# PIC.net
KiCad netlist of a schematic drawn in Altium Designer
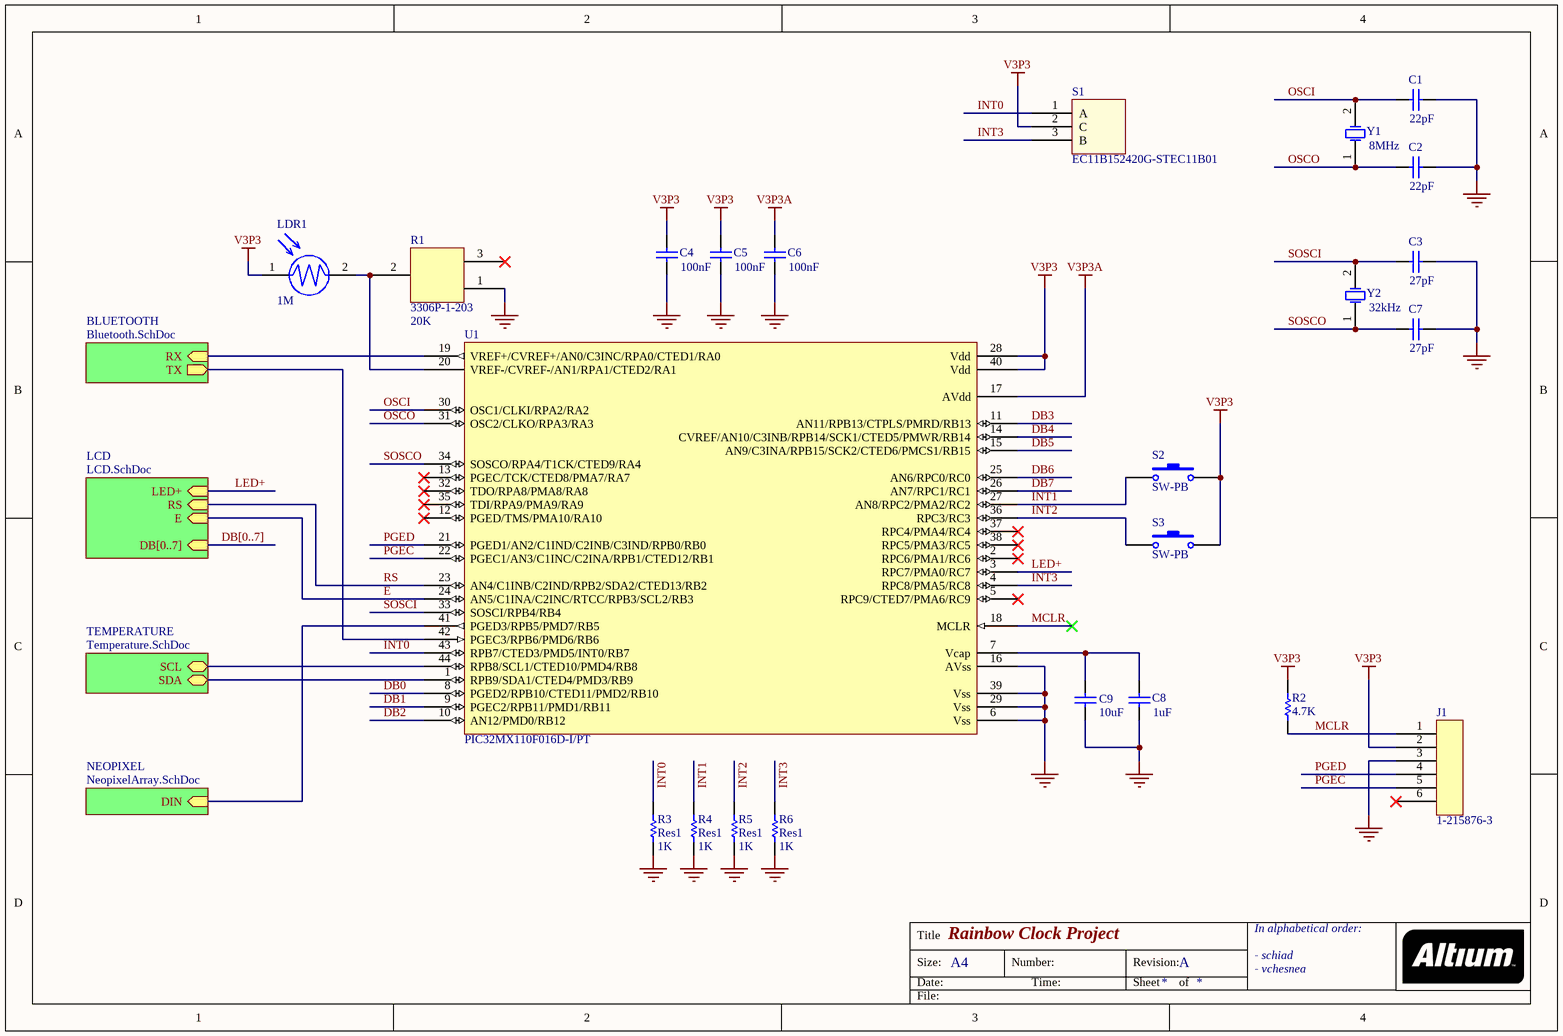
[diagram p0: PIC.SchDoc]

(export (version "E")
  (design (tool "Eeschema 10.0.6"))
  (components
    (comp (ref "C1")
      (value "22pF")
      (footprint "RAD-0.3")
      (description "Capacitor")
      (fields (field (name "Comment") "Cap"))
      (libsource (lib "Miscellaneous Devices") (part "Cap"))
    )
    (comp (ref "C2")
      (value "22pF")
      (footprint "RAD-0.3")
      (description "Capacitor")
      (fields (field (name "Comment") "Cap"))
      (libsource (lib "Miscellaneous Devices") (part "Cap"))
    )
    (comp (ref "C3")
      (value "27pF")
      (footprint "RAD-0.3")
      (description "Capacitor")
      (fields (field (name "Comment") "Cap"))
      (libsource (lib "Miscellaneous Devices") (part "Cap"))
    )
    (comp (ref "C4")
      (value "100nF")
      (footprint "RAD-0.3")
      (description "Capacitor")
      (fields (field (name "Comment") "Cap"))
      (libsource (lib "Miscellaneous Devices") (part "Cap"))
    )
    (comp (ref "C5")
      (value "100nF")
      (footprint "RAD-0.3")
      (description "Capacitor")
      (fields (field (name "Comment") "Cap"))
      (libsource (lib "Miscellaneous Devices") (part "Cap"))
    )
    (comp (ref "C6")
      (value "100nF")
      (footprint "RAD-0.3")
      (description "Capacitor")
      (fields (field (name "Comment") "Cap"))
      (libsource (lib "Miscellaneous Devices") (part "Cap"))
    )
    (comp (ref "C7")
      (value "27pF")
      (footprint "RAD-0.3")
      (description "Capacitor")
      (fields (field (name "Comment") "Cap"))
      (libsource (lib "Miscellaneous Devices") (part "Cap"))
    )
    (comp (ref "C8")
      (value "1uF")
      (footprint "RAD-0.3")
      (description "Capacitor")
      (fields (field (name "Comment") "Cap"))
      (libsource (lib "Miscellaneous Devices") (part "Cap"))
    )
    (comp (ref "C9")
      (value "10uF")
      (footprint "RAD-0.3")
      (description "Capacitor")
      (fields (field (name "Comment") "Cap"))
      (libsource (lib "Miscellaneous Devices") (part "Cap"))
    )
    (comp (ref "J1")
      (value "1-215876-3")
      (description "Tyco 1-215876-3")
      (libsource (lib "Components") (part "1-215876-3"))
    )
    (comp (ref "LDR1")
      (value "1M")
      (description "Photoresistor")
      (fields (field (name "Comment") "LDR"))
      (libsource (lib "Components") (part "LDR"))
    )
    (comp (ref "R1")
      (value "3306P-1-203")
      (footprint "3306P-1-202")
      (description "Trimpot")
      (fields (field (name "ALTIUM_VALUE") "20K"))
      (libsource (lib "Components") (part "3306P-1-202"))
    )
    (comp (ref "R2")
      (value "4.7K")
      (footprint "AXIAL-0.3")
      (description "Resistor")
      (fields (field (name "Comment") "Res1"))
      (libsource (lib "Miscellaneous Devices") (part "Res1"))
    )
    (comp (ref "R3")
      (value "Res1")
      (footprint "AXIAL-0.3")
      (description "Resistor")
      (fields (field (name "ALTIUM_VALUE") "1K"))
      (libsource (lib "Miscellaneous Devices") (part "Res1"))
    )
    (comp (ref "R4")
      (value "Res1")
      (footprint "AXIAL-0.3")
      (description "Resistor")
      (fields (field (name "ALTIUM_VALUE") "1K"))
      (libsource (lib "Miscellaneous Devices") (part "Res1"))
    )
    (comp (ref "R5")
      (value "Res1")
      (footprint "AXIAL-0.3")
      (description "Resistor")
      (fields (field (name "ALTIUM_VALUE") "1K"))
      (libsource (lib "Miscellaneous Devices") (part "Res1"))
    )
    (comp (ref "R6")
      (value "Res1")
      (footprint "AXIAL-0.3")
      (description "Resistor")
      (fields (field (name "ALTIUM_VALUE") "1K"))
      (libsource (lib "Miscellaneous Devices") (part "Res1"))
    )
    (comp (ref "S1")
      (value "EC11B152420G-STEC11B01")
      (footprint "EC11B152420G-STEC11B01")
      (description "Rotary encoder")
      (libsource (lib "Components") (part "EC11B152420G-STEC11B01"))
    )
    (comp (ref "S2")
      (value "SW-PB")
      (footprint "Button")
      (description "Switch")
      (libsource (lib "Miscellaneous Devices") (part "SW-PB"))
    )
    (comp (ref "S3")
      (value "SW-PB")
      (footprint "SPST-2")
      (description "Switch")
      (libsource (lib "Miscellaneous Devices") (part "SW-PB"))
    )
    (comp (ref "U1")
      (value "PIC32MX110F016D-I/PT")
      (description "Microcontroller")
      (libsource (lib "Components") (part "PIC32MX110F016D-I/PT"))
    )
    (comp (ref "Y1")
      (value "8MHz")
      (footprint "R38")
      (description "Crystal Oscillator")
      (fields (field (name "Comment") "XTAL"))
      (libsource (lib "Miscellaneous Devices") (part "XTAL"))
    )
    (comp (ref "Y2")
      (value "32kHz")
      (footprint "R38")
      (description "Crystal Oscillator")
      (fields (field (name "Comment") "XTAL"))
      (libsource (lib "Miscellaneous Devices") (part "XTAL"))
    )
  )
  (nets
    (net (code "1") (name "/DB0") (class "Default")
      (node (ref "U1") (pin "8") (pinfunction "PGED2/RPB10/CTED11/PMD2/RB10_8") (pintype "bidirectional"))
    )
    (net (code "2") (name "/DB1") (class "Default")
      (node (ref "U1") (pin "9") (pinfunction "PGEC2/RPB11/PMD1/RB11_9") (pintype "bidirectional"))
    )
    (net (code "3") (name "/DB2") (class "Default")
      (node (ref "U1") (pin "10") (pinfunction "AN12/PMD0/RB12_10") (pintype "bidirectional"))
    )
    (net (code "4") (name "/DB3") (class "Default")
      (node (ref "U1") (pin "11") (pinfunction "AN11/RPB13/CTPLS/PMRD/RB13_11") (pintype "bidirectional"))
    )
    (net (code "5") (name "/DB4") (class "Default")
      (node (ref "U1") (pin "14") (pinfunction "CVREF/AN10/C3INB/RPB14/SCK1/CTED5/PMWR/RB14_14") (pintype "bidirectional"))
    )
    (net (code "6") (name "/DB5") (class "Default")
      (node (ref "U1") (pin "15") (pinfunction "AN9/C3INA/RPB15/SCK2/CTED6/PMCS1/RB15_15") (pintype "bidirectional"))
    )
    (net (code "7") (name "/DB6") (class "Default")
      (node (ref "U1") (pin "25") (pinfunction "AN6/RPC0/RC0_25") (pintype "bidirectional"))
    )
    (net (code "8") (name "/DB7") (class "Default")
      (node (ref "U1") (pin "26") (pinfunction "AN7/RPC1/RC1_26") (pintype "bidirectional"))
    )
    (net (code "10") (name "/DIN") (class "Default")
      (node (ref "U1") (pin "41") (pinfunction "PGED3/RPB5/PMD7/RB5_41") (pintype "output"))
    )
    (net (code "11") (name "/E") (class "Default")
      (node (ref "U1") (pin "24") (pinfunction "AN5/C1INA/C2INC/RTCC/RPB3/SCL2/RB3_24") (pintype "bidirectional"))
    )
    (net (code "12") (name "/INT0") (class "Default")
      (node (ref "R3") (pin "1") (pinfunction "1_1") (pintype "passive"))
      (node (ref "S1") (pin "1") (pinfunction "A_1") (pintype "passive"))
      (node (ref "U1") (pin "43") (pinfunction "RPB7/CTED3/PMD5/INT0/RB7_43") (pintype "bidirectional"))
    )
    (net (code "13") (name "/INT1") (class "Default")
      (node (ref "R4") (pin "2") (pinfunction "2_2") (pintype "passive"))
      (node (ref "S2") (pin "1") (pinfunction "1_1") (pintype "passive"))
      (node (ref "U1") (pin "27") (pinfunction "AN8/RPC2/PMA2/RC2_27") (pintype "bidirectional"))
    )
    (net (code "14") (name "/INT2") (class "Default")
      (node (ref "R5") (pin "2") (pinfunction "2_2") (pintype "passive"))
      (node (ref "S3") (pin "1") (pinfunction "1_1") (pintype "passive"))
      (node (ref "U1") (pin "36") (pinfunction "RPC3/RC3_36") (pintype "bidirectional"))
    )
    (net (code "15") (name "/INT3") (class "Default")
      (node (ref "R6") (pin "2") (pinfunction "2_2") (pintype "passive"))
      (node (ref "S1") (pin "3") (pinfunction "B_3") (pintype "passive"))
      (node (ref "U1") (pin "4") (pinfunction "RPC8/PMA5/RC8_4") (pintype "bidirectional"))
    )
    (net (code "16") (name "/LED+") (class "Default")
      (node (ref "U1") (pin "3") (pinfunction "RPC7/PMA0/RC7_3") (pintype "bidirectional"))
    )
    (net (code "17") (name "/MCLR") (class "Default")
      (node (ref "J1") (pin "1") (pintype "passive"))
      (node (ref "R2") (pin "1") (pinfunction "1_1") (pintype "passive"))
      (node (ref "U1") (pin "18") (pinfunction "MCLR_18") (pintype "input"))
    )
    (net (code "18") (name "/OSCI") (class "Default")
      (node (ref "C1") (pin "1") (pinfunction "1_1") (pintype "passive"))
      (node (ref "U1") (pin "30") (pinfunction "OSC1/CLKI/RPA2/RA2_30") (pintype "bidirectional"))
      (node (ref "Y1") (pin "2") (pinfunction "OSC2_2") (pintype "passive"))
    )
    (net (code "19") (name "/OSCO") (class "Default")
      (node (ref "C2") (pin "1") (pinfunction "1_1") (pintype "passive"))
      (node (ref "U1") (pin "31") (pinfunction "OSC2/CLKO/RPA3/RA3_31") (pintype "bidirectional"))
      (node (ref "Y1") (pin "1") (pinfunction "OSC1_1") (pintype "passive"))
    )
    (net (code "20") (name "/PGEC") (class "Default")
      (node (ref "J1") (pin "5") (pintype "passive"))
      (node (ref "U1") (pin "22") (pinfunction "PGEC1/AN3/C1INC/C2INA/RPB1/CTED12/RB1_22") (pintype "bidirectional"))
    )
    (net (code "21") (name "/PGED") (class "Default")
      (node (ref "J1") (pin "4") (pintype "passive"))
      (node (ref "U1") (pin "21") (pinfunction "PGED1/AN2/C1IND/C2INB/C3IND/RPB0/RB0_21") (pintype "bidirectional"))
    )
    (net (code "22") (name "/RS") (class "Default")
      (node (ref "U1") (pin "23") (pinfunction "AN4/C1INB/C2IND/RPB2/SDA2/CTED13/RB2_23") (pintype "bidirectional"))
    )
    (net (code "23") (name "/RX") (class "Default")
      (node (ref "U1") (pin "19") (pinfunction "VREF+/CVREF+/AN0/C3INC/RPA0/CTED1/RA0_19") (pintype "output"))
    )
    (net (code "24") (name "/SCL") (class "Default")
      (node (ref "U1") (pin "44") (pinfunction "RPB8/SCL1/CTED10/PMD4/RB8_44") (pintype "bidirectional"))
    )
    (net (code "25") (name "/SDA") (class "Default")
      (node (ref "U1") (pin "1") (pinfunction "RPB9/SDA1/CTED4/PMD3/RB9_1") (pintype "bidirectional"))
    )
    (net (code "26") (name "/SOSCI") (class "Default")
      (node (ref "C3") (pin "1") (pinfunction "1_1") (pintype "passive"))
      (node (ref "U1") (pin "33") (pinfunction "SOSCI/RPB4/RB4_33") (pintype "bidirectional"))
      (node (ref "Y2") (pin "2") (pinfunction "OSC2_2") (pintype "passive"))
    )
    (net (code "27") (name "/SOSCO") (class "Default")
      (node (ref "C7") (pin "1") (pinfunction "1_1") (pintype "passive"))
      (node (ref "U1") (pin "34") (pinfunction "SOSCO/RPA4/T1CK/CTED9/RA4_34") (pintype "bidirectional"))
      (node (ref "Y2") (pin "1") (pinfunction "OSC1_1") (pintype "passive"))
    )
    (net (code "28") (name "/TX") (class "Default")
      (node (ref "U1") (pin "42") (pinfunction "PGEC3/RPB6/PMD6/RB6_42") (pintype "input"))
    )
    (net (code "29") (name "GND") (class "Default")
      (node (ref "C1") (pin "2") (pinfunction "2_2") (pintype "passive"))
      (node (ref "C2") (pin "2") (pinfunction "2_2") (pintype "passive"))
      (node (ref "C3") (pin "2") (pinfunction "2_2") (pintype "passive"))
      (node (ref "C4") (pin "1") (pinfunction "1_1") (pintype "passive"))
      (node (ref "C5") (pin "1") (pinfunction "1_1") (pintype "passive"))
      (node (ref "C6") (pin "1") (pinfunction "1_1") (pintype "passive"))
      (node (ref "C7") (pin "2") (pinfunction "2_2") (pintype "passive"))
      (node (ref "J1") (pin "3") (pintype "passive"))
      (node (ref "R1") (pin "1") (pinfunction "1_1") (pintype "power_in"))
      (node (ref "R3") (pin "2") (pinfunction "2_2") (pintype "passive"))
      (node (ref "R4") (pin "1") (pinfunction "1_1") (pintype "passive"))
      (node (ref "R5") (pin "1") (pinfunction "1_1") (pintype "passive"))
      (node (ref "R6") (pin "1") (pinfunction "1_1") (pintype "passive"))
    )
    (net (code "30") (name "Net-(U1-VREF-{slash}CVREF-{slash}AN1{slash}RPA1{slash}CTED2{slash}RA1)") (class "Default")
      (node (ref "LDR1") (pin "2") (pinfunction "2_2") (pintype "power_in"))
      (node (ref "R1") (pin "2") (pinfunction "2_2") (pintype "power_in"))
      (node (ref "U1") (pin "20") (pinfunction "VREF-/CVREF-/AN1/RPA1/CTED2/RA1_20") (pintype "passive"))
    )
    (net (code "31") (name "Net-(U1-Vcap)") (class "Default")
      (node (ref "C8") (pin "2") (pinfunction "2_2") (pintype "passive"))
      (node (ref "C9") (pin "2") (pinfunction "2_2") (pintype "passive"))
      (node (ref "U1") (pin "7") (pinfunction "Vcap_7") (pintype "power_in"))
    )
    (net (code "32") (name "V3P3") (class "Default")
      (node (ref "C4") (pin "2") (pinfunction "2_2") (pintype "passive"))
      (node (ref "C5") (pin "2") (pinfunction "2_2") (pintype "passive"))
      (node (ref "J1") (pin "2") (pintype "passive"))
      (node (ref "LDR1") (pin "1") (pinfunction "1_1") (pintype "power_in"))
      (node (ref "R2") (pin "2") (pinfunction "2_2") (pintype "passive"))
      (node (ref "S1") (pin "2") (pinfunction "C_2") (pintype "passive"))
      (node (ref "S2") (pin "2") (pinfunction "2_2") (pintype "passive"))
      (node (ref "S3") (pin "2") (pinfunction "2_2") (pintype "passive"))
      (node (ref "U1") (pin "28") (pinfunction "Vdd_28") (pintype "power_in"))
      (node (ref "U1") (pin "40") (pinfunction "Vdd_40") (pintype "power_in"))
    )
    (net (code "33") (name "V3P3A") (class "Default")
      (node (ref "C6") (pin "2") (pinfunction "2_2") (pintype "passive"))
      (node (ref "U1") (pin "17") (pinfunction "AVdd_17") (pintype "power_in"))
    )
    (net (code "34") (name "VSS") (class "Default")
      (node (ref "C8") (pin "1") (pinfunction "1_1") (pintype "passive"))
      (node (ref "C9") (pin "1") (pinfunction "1_1") (pintype "passive"))
      (node (ref "U1") (pin "16") (pinfunction "AVss_16") (pintype "power_in"))
      (node (ref "U1") (pin "29") (pinfunction "Vss_29") (pintype "power_in"))
      (node (ref "U1") (pin "39") (pinfunction "Vss_39") (pintype "power_in"))
      (node (ref "U1") (pin "6") (pinfunction "Vss_6") (pintype "power_in"))
    )
    (net (code "35") (name "unconnected-(J1-Pad6)") (class "Default")
      (node (ref "J1") (pin "6") (pintype "passive+no_connect"))
    )
    (net (code "36") (name "unconnected-(R1-Pad3)") (class "Default")
      (node (ref "R1") (pin "3") (pinfunction "3_3") (pintype "power_in+no_connect"))
    )
    (net (code "37") (name "unconnected-(U1-PGEC{slash}TCK{slash}CTED8{slash}PMA7{slash}RA7-Pad13)") (class "Default")
      (node (ref "U1") (pin "13") (pinfunction "PGEC/TCK/CTED8/PMA7/RA7_13") (pintype "bidirectional+no_connect"))
    )
    (net (code "38") (name "unconnected-(U1-PGED{slash}TMS{slash}PMA10{slash}RA10-Pad12)") (class "Default")
      (node (ref "U1") (pin "12") (pinfunction "PGED/TMS/PMA10/RA10_12") (pintype "bidirectional+no_connect"))
    )
    (net (code "39") (name "unconnected-(U1-RPC4{slash}PMA4{slash}RC4-Pad37)") (class "Default")
      (node (ref "U1") (pin "37") (pinfunction "RPC4/PMA4/RC4_37") (pintype "bidirectional+no_connect"))
    )
    (net (code "40") (name "unconnected-(U1-RPC5{slash}PMA3{slash}RC5-Pad38)") (class "Default")
      (node (ref "U1") (pin "38") (pinfunction "RPC5/PMA3/RC5_38") (pintype "bidirectional+no_connect"))
    )
    (net (code "41") (name "unconnected-(U1-RPC6{slash}PMA1{slash}RC6-Pad2)") (class "Default")
      (node (ref "U1") (pin "2") (pinfunction "RPC6/PMA1/RC6_2") (pintype "bidirectional+no_connect"))
    )
    (net (code "42") (name "unconnected-(U1-RPC9{slash}CTED7{slash}PMA6{slash}RC9-Pad5)") (class "Default")
      (node (ref "U1") (pin "5") (pinfunction "RPC9/CTED7/PMA6/RC9_5") (pintype "bidirectional+no_connect"))
    )
    (net (code "43") (name "unconnected-(U1-TDI{slash}RPA9{slash}PMA9{slash}RA9-Pad35)") (class "Default")
      (node (ref "U1") (pin "35") (pinfunction "TDI/RPA9/PMA9/RA9_35") (pintype "bidirectional+no_connect"))
    )
    (net (code "44") (name "unconnected-(U1-TDO{slash}RPA8{slash}PMA8{slash}RA8-Pad32)") (class "Default")
      (node (ref "U1") (pin "32") (pinfunction "TDO/RPA8/PMA8/RA8_32") (pintype "bidirectional+no_connect"))
    )
  )
)
